# Sheet1.net
KiCad netlist of a schematic drawn in Altium Designer
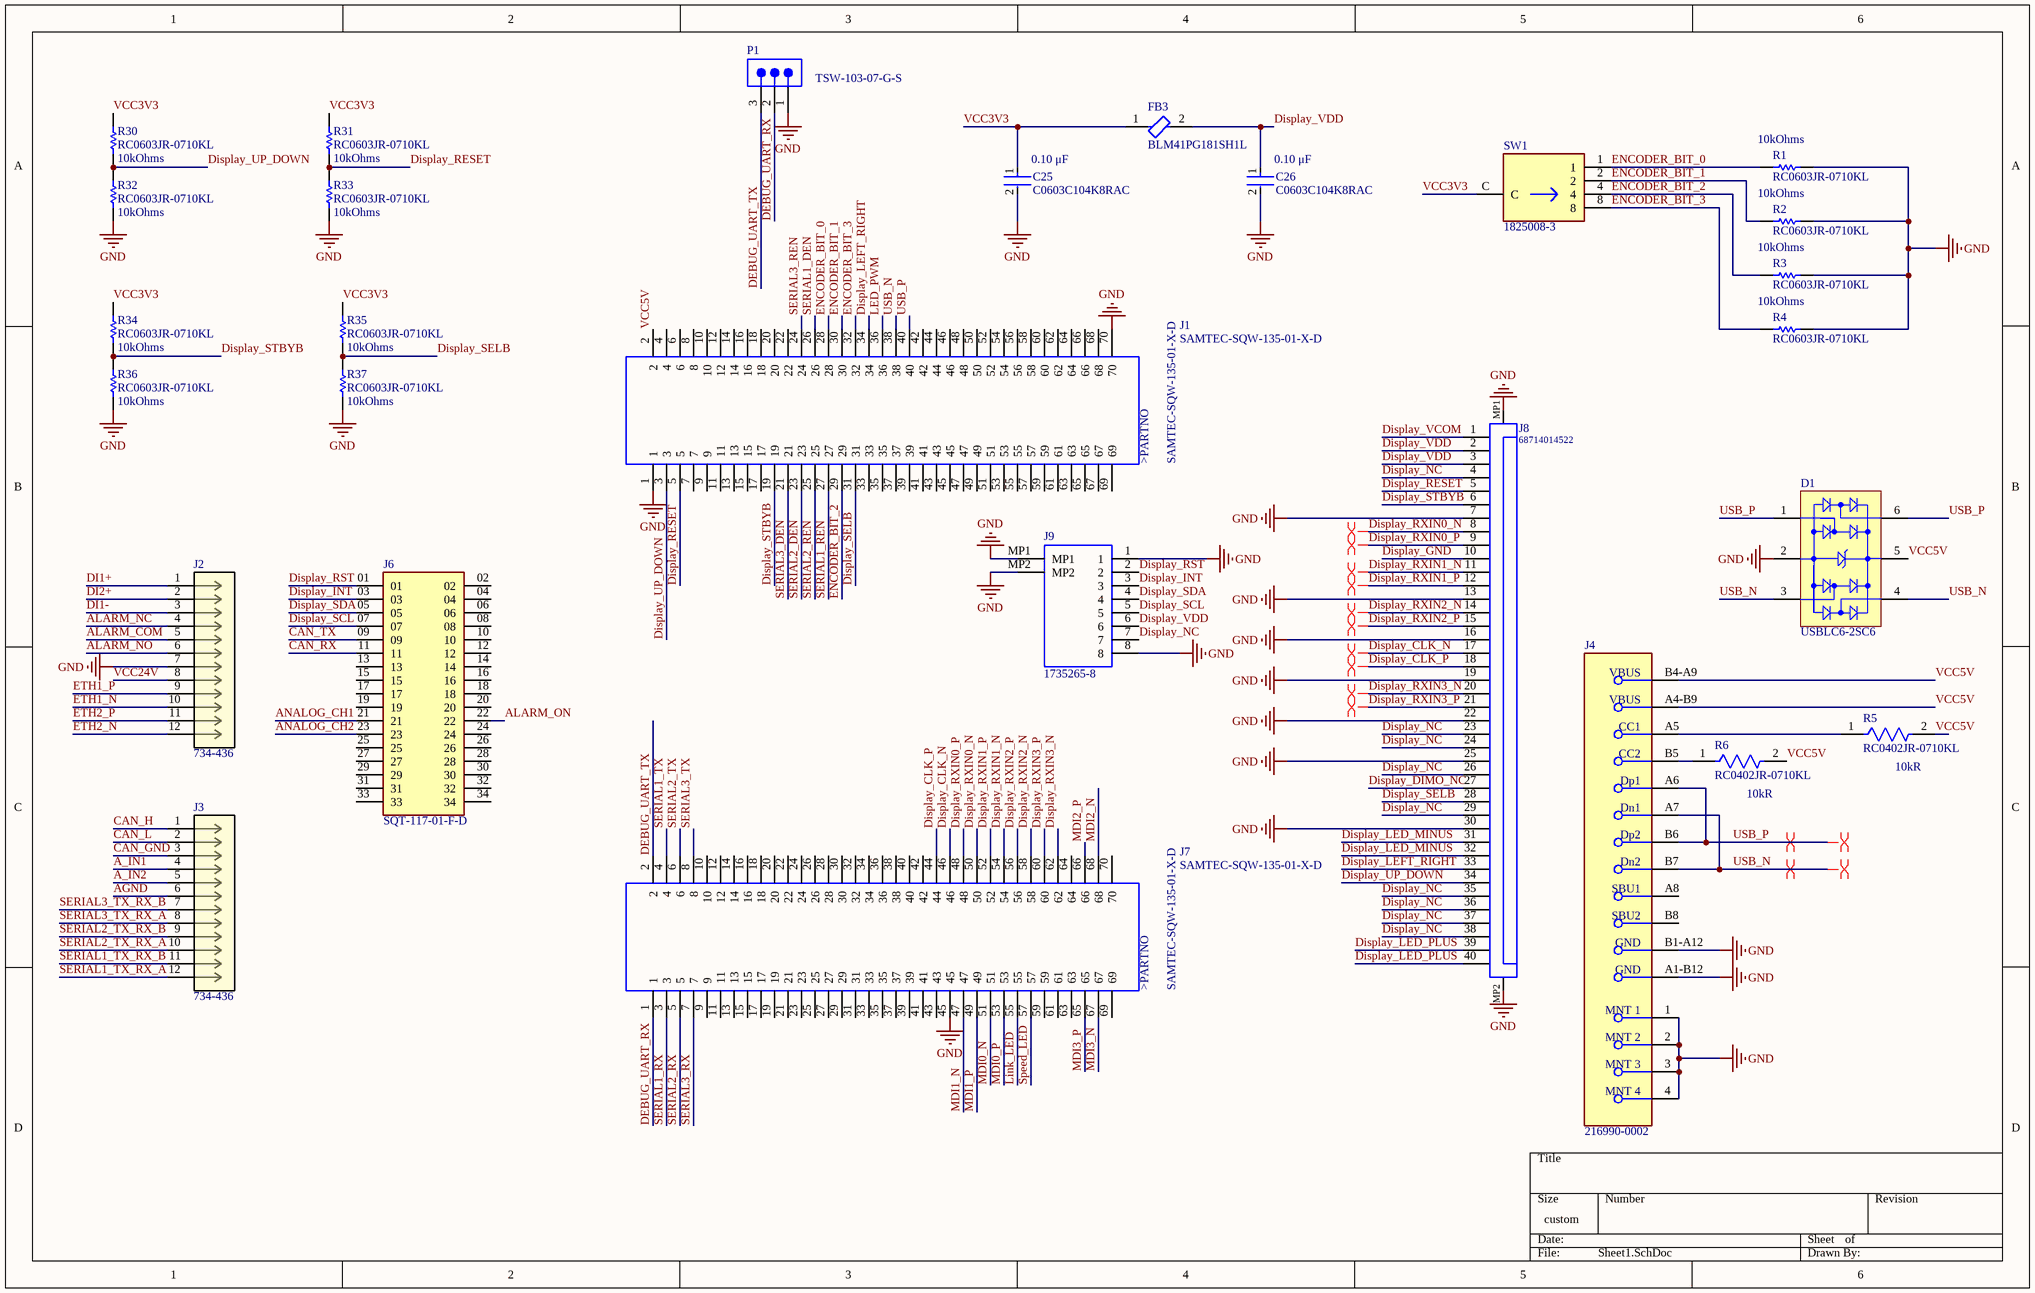
[diagram p0: Sheet1.SchDoc]

(export (version "E")
  (design (tool "Eeschema 10.0.6"))
  (components
    (comp (ref "C25")
      (value "C0603C104K8RAC")
      (footprint "FP-C0603C-CF-MFG")
      (description "C0603 0.10 μF X7R 30ppm/°C 10.00% 10 V")
      (fields
        (field (name "MANUFACTURER") "KEMET")
        (field (name "CAPACITANCE") "0.10 μF")
        (field (name "OCTOPART") "https://octopart.com/c0603c104k8rac-kemet-1325403")
      )
      (libsource (lib "Altium Content Vault") (part "b4654b650e69147ec39a6b967a45e02"))
    )
    (comp (ref "C26")
      (value "C0603C104K8RAC")
      (footprint "FP-C0603C-CF-MFG")
      (description "C0603 0.10 μF X7R 30ppm/°C 10.00% 10 V")
      (fields
        (field (name "MANUFACTURER") "KEMET")
        (field (name "CAPACITANCE") "0.10 μF")
        (field (name "OCTOPART") "https://octopart.com/c0603c104k8rac-kemet-1325403")
      )
      (libsource (lib "Altium Content Vault") (part "b4654b650e69147ec39a6b967a45e02"))
    )
    (comp (ref "D1")
      (value "USBLC6-2SC6")
      (footprint "STM-SOT23-6L_V")
      (description "Very low capacitance ESD protection, 3.5 pF, -40 to 125 degC, 6-Pin SOT23, RoHS, Tape and Reel")
      (fields (field (name "MANUFACTURER") "STMicroelectronics"))
      (libsource (lib "Altium Content Vault") (part "STM-USB_DVI_HDMIULC6-4SC6X-SOT23-6L"))
    )
    (comp (ref "FB3")
      (value "BLM41PG181SH1L")
      (footprint "FP-BLM41-0_2-a1_2-MFG")
      (description "Ferrite Bead, 1806, 180Ω @ 100MHz, 25%, 0.02Ω, 3.5A")
      (fields (field (name "TOLERANCE") "25%"))
      (libsource (lib "Altium Content Vault") (part "5f30dd21d616792df468990f7003faa"))
    )
    (comp (ref "J1")
      (value "SAMTEC-SQW-135-01-X-D")
      (footprint "SAMTEC-SQW-135-01-X-D")
      (libsource (lib "Schlib2") (part "SAMTEC-SQW-135-01-X-D"))
    )
    (comp (ref "J2")
      (value "734-436")
      (footprint "CONN12_734-436_WAG")
      (description "No Description Available")
      (fields (field (name "COPYRIGHT") "Copyright (C) 2022 Ultra Librarian. All rights reserved."))
      (libsource (lib "Schlib2") (part "734-436"))
    )
    (comp (ref "J3")
      (value "734-436")
      (footprint "CONN12_734-436_WAG")
      (description "No Description Available")
      (fields (field (name "COPYRIGHT") "Copyright (C) 2022 Ultra Librarian. All rights reserved."))
      (libsource (lib "Schlib2") (part "734-436"))
    )
    (comp (ref "J4")
      (value "216990-0002")
      (footprint "FP-216990-0002-MFG")
      (description "CONN RCP USB2.0 TYP C 24P SMD RA")
      (libsource (lib "Altium Content Vault") (part "7e081d3bdd84dd7df1daf8a7a06d5b3"))
    )
    (comp (ref "J6")
      (value "SQT-117-01-F-D")
      (footprint "SAMTEC_SQT-117-01-F-D")
      (fields (field (name "MF") "Samtec"))
      (libsource (lib "Schlib2") (part "SQT-117-01-F-D"))
    )
    (comp (ref "J7")
      (value "SAMTEC-SQW-135-01-X-D")
      (footprint "SAMTEC-SQW-135-01-X-D")
      (libsource (lib "Schlib2") (part "SAMTEC-SQW-135-01-X-D"))
    )
    (comp (ref "J8")
      (value "68714014522")
      (footprint "68714014522")
      (description "SMT ZIF Connectors WR-FPC, Horizontal, Bottom Contact, pitch 0.5 mm, 40 pins")
      (fields (field (name "MANUFACTURER") "Wurth Elektronik") (field (name "PUBLISHER") "WurthElektronik"))
      (libsource (lib "Altium Content Vault") (part "WE-6871401XXX22-40"))
    )
    (comp (ref "J9")
      (value "1735265-8")
      (footprint "17352658")
      (description "1MM FPC HORZ.BOTTOM CONT.ASSY 8P (Au)")
      (fields (field (name "MOUSER PART NUMBER") "571-1735265-8"))
      (libsource (lib "Schlib2") (part "1735265-8"))
    )
    (comp (ref "P1")
      (value "TSW-103-07-G-S")
      (footprint "SMTC-TSW-103-07-X-S")
      (description "0.025\" SQ Post Header, Through-hole, Vertical, -55 to 125 degC, 2.54 mm Pitch, 3-Pin, Male, RoHS")
      (fields (field (name "MANUFACTURER") "Samtec"))
      (libsource (lib "Altium Content Vault") (part "SMTC-TSW-103-X-X-S-X"))
    )
    (comp (ref "R1")
      (value "RC0603JR-0710KL")
      (footprint "RESC1608X55X25ML10T15")
      (description "Resistor, 10 KOhm, +/- 5%, 100 mW, -55 to 155 degC, 0603 (1608 Metric), RoHS, Tape and Reel")
      (fields
        (field (name "RESISTANCE") "10kOhms")
        (field (name "MANUFACTURER") "Yageo")
        (field (name "TOLERANCE") "5%")
      )
      (libsource (lib "Altium Content Vault") (part "RES-2"))
    )
    (comp (ref "R2")
      (value "RC0603JR-0710KL")
      (footprint "RESC1608X55X25ML10T15")
      (description "Resistor, 10 KOhm, +/- 5%, 100 mW, -55 to 155 degC, 0603 (1608 Metric), RoHS, Tape and Reel")
      (fields
        (field (name "RESISTANCE") "10kOhms")
        (field (name "MANUFACTURER") "Yageo")
        (field (name "TOLERANCE") "5%")
      )
      (libsource (lib "Altium Content Vault") (part "RES-2"))
    )
    (comp (ref "R3")
      (value "RC0603JR-0710KL")
      (footprint "RESC1608X55X25ML10T15")
      (description "Resistor, 10 KOhm, +/- 5%, 100 mW, -55 to 155 degC, 0603 (1608 Metric), RoHS, Tape and Reel")
      (fields
        (field (name "RESISTANCE") "10kOhms")
        (field (name "MANUFACTURER") "Yageo")
        (field (name "TOLERANCE") "5%")
      )
      (libsource (lib "Altium Content Vault") (part "RES-2"))
    )
    (comp (ref "R4")
      (value "RC0603JR-0710KL")
      (footprint "RESC1608X55X25ML10T15")
      (description "Resistor, 10 KOhm, +/- 5%, 100 mW, -55 to 155 degC, 0603 (1608 Metric), RoHS, Tape and Reel")
      (fields
        (field (name "RESISTANCE") "10kOhms")
        (field (name "MANUFACTURER") "Yageo")
        (field (name "TOLERANCE") "5%")
      )
      (libsource (lib "Altium Content Vault") (part "RES-2"))
    )
    (comp (ref "R5")
      (value "RC0402JR-0710KL")
      (footprint "FP-RC0402-0_4-IPC_C")
      (description "RES 10K OHM 5% 1/16W 0402")
      (fields (field (name "RESISTANCE") "10kR") (field (name "TOLERANCE") "5%"))
      (libsource (lib "Altium Content Vault") (part "1029c3af85768c4190bb7ad29bc67b5"))
    )
    (comp (ref "R6")
      (value "RC0402JR-0710KL")
      (footprint "FP-RC0402-0_4-IPC_C")
      (description "RES 10K OHM 5% 1/16W 0402")
      (fields (field (name "RESISTANCE") "10kR") (field (name "TOLERANCE") "5%"))
      (libsource (lib "Altium Content Vault") (part "1029c3af85768c4190bb7ad29bc67b5"))
    )
    (comp (ref "R30")
      (value "RC0603JR-0710KL")
      (footprint "RESC1608X55X25ML10T15")
      (description "Resistor, 10 KOhm, +/- 5%, 100 mW, -55 to 155 degC, 0603 (1608 Metric), RoHS, Tape and Reel")
      (fields
        (field (name "RESISTANCE") "10kOhms")
        (field (name "MANUFACTURER") "Yageo")
        (field (name "TOLERANCE") "5%")
      )
      (libsource (lib "Altium Content Vault") (part "RES-2"))
    )
    (comp (ref "R31")
      (value "RC0603JR-0710KL")
      (footprint "RESC1608X55X25ML10T15")
      (description "Resistor, 10 KOhm, +/- 5%, 100 mW, -55 to 155 degC, 0603 (1608 Metric), RoHS, Tape and Reel")
      (fields
        (field (name "RESISTANCE") "10kOhms")
        (field (name "MANUFACTURER") "Yageo")
        (field (name "TOLERANCE") "5%")
      )
      (libsource (lib "Altium Content Vault") (part "RES-2"))
    )
    (comp (ref "R32")
      (value "RC0603JR-0710KL")
      (footprint "RESC1608X55X25ML10T15")
      (description "Resistor, 10 KOhm, +/- 5%, 100 mW, -55 to 155 degC, 0603 (1608 Metric), RoHS, Tape and Reel")
      (fields
        (field (name "RESISTANCE") "10kOhms")
        (field (name "MANUFACTURER") "Yageo")
        (field (name "TOLERANCE") "5%")
      )
      (libsource (lib "Altium Content Vault") (part "RES-2"))
    )
    (comp (ref "R33")
      (value "RC0603JR-0710KL")
      (footprint "RESC1608X55X25ML10T15")
      (description "Resistor, 10 KOhm, +/- 5%, 100 mW, -55 to 155 degC, 0603 (1608 Metric), RoHS, Tape and Reel")
      (fields
        (field (name "RESISTANCE") "10kOhms")
        (field (name "MANUFACTURER") "Yageo")
        (field (name "TOLERANCE") "5%")
      )
      (libsource (lib "Altium Content Vault") (part "RES-2"))
    )
    (comp (ref "R34")
      (value "RC0603JR-0710KL")
      (footprint "RESC1608X55X25ML10T15")
      (description "Resistor, 10 KOhm, +/- 5%, 100 mW, -55 to 155 degC, 0603 (1608 Metric), RoHS, Tape and Reel")
      (fields
        (field (name "RESISTANCE") "10kOhms")
        (field (name "MANUFACTURER") "Yageo")
        (field (name "TOLERANCE") "5%")
      )
      (libsource (lib "Altium Content Vault") (part "RES-2"))
    )
    (comp (ref "R35")
      (value "RC0603JR-0710KL")
      (footprint "RESC1608X55X25ML10T15")
      (description "Resistor, 10 KOhm, +/- 5%, 100 mW, -55 to 155 degC, 0603 (1608 Metric), RoHS, Tape and Reel")
      (fields
        (field (name "RESISTANCE") "10kOhms")
        (field (name "MANUFACTURER") "Yageo")
        (field (name "TOLERANCE") "5%")
      )
      (libsource (lib "Altium Content Vault") (part "RES-2"))
    )
    (comp (ref "R36")
      (value "RC0603JR-0710KL")
      (footprint "RESC1608X55X25ML10T15")
      (description "Resistor, 10 KOhm, +/- 5%, 100 mW, -55 to 155 degC, 0603 (1608 Metric), RoHS, Tape and Reel")
      (fields
        (field (name "RESISTANCE") "10kOhms")
        (field (name "MANUFACTURER") "Yageo")
        (field (name "TOLERANCE") "5%")
      )
      (libsource (lib "Altium Content Vault") (part "RES-2"))
    )
    (comp (ref "R37")
      (value "RC0603JR-0710KL")
      (footprint "RESC1608X55X25ML10T15")
      (description "Resistor, 10 KOhm, +/- 5%, 100 mW, -55 to 155 degC, 0603 (1608 Metric), RoHS, Tape and Reel")
      (fields
        (field (name "RESISTANCE") "10kOhms")
        (field (name "MANUFACTURER") "Yageo")
        (field (name "TOLERANCE") "5%")
      )
      (libsource (lib "Altium Content Vault") (part "RES-2"))
    )
    (comp (ref "SW1")
      (value "1825008-3")
      (footprint "FP-1825008-3-MFG")
      (description "SW ROTARY DIP HEX COMP 0.4VA 20V")
      (libsource (lib "Altium Content Vault") (part "f1b16a2328e8568533cbbc73886a3cd"))
    )
  )
  (nets
    (net (code "1") (name "/AGND") (class "Default")
      (node (ref "J3") (pin "6") (pinfunction "6_6") (pintype "passive"))
    )
    (net (code "2") (name "/ALARM_COM") (class "Default")
      (node (ref "J2") (pin "5") (pinfunction "5_5") (pintype "passive"))
    )
    (net (code "3") (name "/ALARM_NC") (class "Default")
      (node (ref "J2") (pin "4") (pinfunction "4_4") (pintype "passive"))
    )
    (net (code "4") (name "/ALARM_NO") (class "Default")
      (node (ref "J2") (pin "6") (pinfunction "6_6") (pintype "passive"))
    )
    (net (code "5") (name "/ALARM_ON") (class "Default")
      (node (ref "J6") (pin "22") (pinfunction "22_22") (pintype "passive"))
    )
    (net (code "6") (name "/ANALOG_CH1") (class "Default")
      (node (ref "J6") (pin "21") (pinfunction "21_21") (pintype "passive"))
    )
    (net (code "7") (name "/ANALOG_CH2") (class "Default")
      (node (ref "J6") (pin "23") (pinfunction "23_23") (pintype "passive"))
    )
    (net (code "8") (name "/A_IN1") (class "Default")
      (node (ref "J3") (pin "4") (pinfunction "4_4") (pintype "passive"))
    )
    (net (code "9") (name "/A_IN2") (class "Default")
      (node (ref "J3") (pin "5") (pinfunction "5_5") (pintype "passive"))
    )
    (net (code "10") (name "/CAN_GND") (class "Default")
      (node (ref "J3") (pin "3") (pinfunction "3_3") (pintype "passive"))
    )
    (net (code "11") (name "/CAN_H") (class "Default")
      (node (ref "J3") (pin "1") (pinfunction "1_1") (pintype "passive"))
    )
    (net (code "12") (name "/CAN_L") (class "Default")
      (node (ref "J3") (pin "2") (pinfunction "2_2") (pintype "passive"))
    )
    (net (code "13") (name "/CAN_RX") (class "Default")
      (node (ref "J6") (pin "11") (pinfunction "11_11") (pintype "passive"))
    )
    (net (code "14") (name "/CAN_TX") (class "Default")
      (node (ref "J6") (pin "09") (pinfunction "09_09") (pintype "passive"))
    )
    (net (code "15") (name "/DEBUG_UART_RX") (class "Default")
      (node (ref "J7") (pin "1") (pinfunction "1_1") (pintype "passive"))
      (node (ref "P1") (pin "2") (pinfunction "2_2") (pintype "passive"))
    )
    (net (code "16") (name "/DEBUG_UART_TX") (class "Default")
      (node (ref "J7") (pin "2") (pinfunction "2_2") (pintype "passive"))
      (node (ref "P1") (pin "3") (pinfunction "3_3") (pintype "passive"))
    )
    (net (code "17") (name "/DI1+") (class "Default")
      (node (ref "J2") (pin "1") (pinfunction "1_1") (pintype "passive"))
    )
    (net (code "18") (name "/DI1-") (class "Default")
      (node (ref "J2") (pin "3") (pinfunction "3_3") (pintype "passive"))
    )
    (net (code "19") (name "/DI2+") (class "Default")
      (node (ref "J2") (pin "2") (pinfunction "2_2") (pintype "passive"))
    )
    (net (code "20") (name "/Display_CLK_N") (class "Default")
      (node (ref "J7") (pin "46") (pinfunction "46_46") (pintype "passive"))
      (node (ref "J8") (pin "17") (pinfunction "17_17") (pintype "passive"))
    )
    (net (code "21") (name "/Display_CLK_P") (class "Default")
      (node (ref "J7") (pin "44") (pinfunction "44_44") (pintype "passive"))
      (node (ref "J8") (pin "18") (pinfunction "18_18") (pintype "passive"))
    )
    (net (code "22") (name "/Display_DIMO_NC") (class "Default")
      (node (ref "J8") (pin "27") (pinfunction "27_27") (pintype "passive"))
    )
    (net (code "23") (name "/Display_GND") (class "Default")
      (node (ref "J8") (pin "10") (pinfunction "10_10") (pintype "passive"))
    )
    (net (code "24") (name "/Display_INT") (class "Default")
      (node (ref "J6") (pin "03") (pinfunction "03_03") (pintype "passive"))
      (node (ref "J9") (pin "3") (pinfunction "3_3") (pintype "passive"))
    )
    (net (code "25") (name "/Display_LED_MINUS") (class "Default")
      (node (ref "J8") (pin "31") (pinfunction "31_31") (pintype "passive"))
      (node (ref "J8") (pin "32") (pinfunction "32_32") (pintype "passive"))
    )
    (net (code "26") (name "/Display_LED_PLUS") (class "Default")
      (node (ref "J8") (pin "39") (pinfunction "39_39") (pintype "passive"))
      (node (ref "J8") (pin "40") (pinfunction "40_40") (pintype "passive"))
    )
    (net (code "27") (name "/Display_LEFT_RIGHT") (class "Default")
      (node (ref "J1") (pin "34") (pinfunction "34_34") (pintype "passive"))
      (node (ref "J8") (pin "33") (pinfunction "33_33") (pintype "passive"))
    )
    (net (code "28") (name "/Display_NC") (class "Default")
      (node (ref "J8") (pin "23") (pinfunction "23_23") (pintype "passive"))
      (node (ref "J8") (pin "24") (pinfunction "24_24") (pintype "passive"))
      (node (ref "J8") (pin "26") (pinfunction "26_26") (pintype "passive"))
      (node (ref "J8") (pin "29") (pinfunction "29_29") (pintype "passive"))
      (node (ref "J8") (pin "35") (pinfunction "35_35") (pintype "passive"))
      (node (ref "J8") (pin "36") (pinfunction "36_36") (pintype "passive"))
      (node (ref "J8") (pin "37") (pinfunction "37_37") (pintype "passive"))
      (node (ref "J8") (pin "38") (pinfunction "38_38") (pintype "passive"))
      (node (ref "J8") (pin "4") (pinfunction "4_4") (pintype "passive"))
      (node (ref "J9") (pin "7") (pinfunction "7_7") (pintype "passive"))
    )
    (net (code "29") (name "/Display_RESET") (class "Default")
      (node (ref "J1") (pin "5") (pinfunction "5_5") (pintype "passive"))
      (node (ref "J8") (pin "5") (pinfunction "5_5") (pintype "passive"))
      (node (ref "R31") (pin "1") (pinfunction "1_1") (pintype "passive"))
      (node (ref "R33") (pin "2") (pinfunction "2_2") (pintype "passive"))
    )
    (net (code "30") (name "/Display_RST") (class "Default")
      (node (ref "J6") (pin "01") (pinfunction "01_01") (pintype "passive"))
      (node (ref "J9") (pin "2") (pinfunction "2_2") (pintype "passive"))
    )
    (net (code "31") (name "/Display_RXIN0_N") (class "Default")
      (node (ref "J7") (pin "50") (pinfunction "50_50") (pintype "passive"))
      (node (ref "J8") (pin "8") (pinfunction "8_8") (pintype "passive"))
    )
    (net (code "32") (name "/Display_RXIN0_P") (class "Default")
      (node (ref "J7") (pin "48") (pinfunction "48_48") (pintype "passive"))
      (node (ref "J8") (pin "9") (pinfunction "9_9") (pintype "passive"))
    )
    (net (code "33") (name "/Display_RXIN1_N") (class "Default")
      (node (ref "J7") (pin "54") (pinfunction "54_54") (pintype "passive"))
      (node (ref "J8") (pin "11") (pinfunction "11_11") (pintype "passive"))
    )
    (net (code "34") (name "/Display_RXIN1_P") (class "Default")
      (node (ref "J7") (pin "52") (pinfunction "52_52") (pintype "passive"))
      (node (ref "J8") (pin "12") (pinfunction "12_12") (pintype "passive"))
    )
    (net (code "35") (name "/Display_RXIN2_N") (class "Default")
      (node (ref "J7") (pin "58") (pinfunction "58_58") (pintype "passive"))
      (node (ref "J8") (pin "14") (pinfunction "14_14") (pintype "passive"))
    )
    (net (code "36") (name "/Display_RXIN2_P") (class "Default")
      (node (ref "J7") (pin "56") (pinfunction "56_56") (pintype "passive"))
      (node (ref "J8") (pin "15") (pinfunction "15_15") (pintype "passive"))
    )
    (net (code "37") (name "/Display_RXIN3_N") (class "Default")
      (node (ref "J7") (pin "62") (pinfunction "62_62") (pintype "passive"))
      (node (ref "J8") (pin "20") (pinfunction "20_20") (pintype "passive"))
    )
    (net (code "38") (name "/Display_RXIN3_P") (class "Default")
      (node (ref "J7") (pin "60") (pinfunction "60_60") (pintype "passive"))
      (node (ref "J8") (pin "21") (pinfunction "21_21") (pintype "passive"))
    )
    (net (code "39") (name "/Display_SCL") (class "Default")
      (node (ref "J6") (pin "07") (pinfunction "07_07") (pintype "passive"))
      (node (ref "J9") (pin "5") (pinfunction "5_5") (pintype "passive"))
    )
    (net (code "40") (name "/Display_SDA") (class "Default")
      (node (ref "J6") (pin "05") (pinfunction "05_05") (pintype "passive"))
      (node (ref "J9") (pin "4") (pinfunction "4_4") (pintype "passive"))
    )
    (net (code "41") (name "/Display_SELB") (class "Default")
      (node (ref "J1") (pin "31") (pinfunction "31_31") (pintype "passive"))
      (node (ref "J8") (pin "28") (pinfunction "28_28") (pintype "passive"))
      (node (ref "R35") (pin "1") (pinfunction "1_1") (pintype "passive"))
      (node (ref "R37") (pin "2") (pinfunction "2_2") (pintype "passive"))
    )
    (net (code "42") (name "/Display_STBYB") (class "Default")
      (node (ref "J1") (pin "19") (pinfunction "19_19") (pintype "passive"))
      (node (ref "J8") (pin "6") (pinfunction "6_6") (pintype "passive"))
      (node (ref "R34") (pin "1") (pinfunction "1_1") (pintype "passive"))
      (node (ref "R36") (pin "2") (pinfunction "2_2") (pintype "passive"))
    )
    (net (code "43") (name "/Display_UP_DOWN") (class "Default")
      (node (ref "J1") (pin "3") (pinfunction "3_3") (pintype "passive"))
      (node (ref "J8") (pin "34") (pinfunction "34_34") (pintype "passive"))
      (node (ref "R30") (pin "1") (pinfunction "1_1") (pintype "passive"))
      (node (ref "R32") (pin "2") (pinfunction "2_2") (pintype "passive"))
    )
    (net (code "44") (name "/Display_VCOM") (class "Default")
      (node (ref "J8") (pin "1") (pinfunction "1_1") (pintype "passive"))
    )
    (net (code "45") (name "/Display_VDD") (class "Default")
      (node (ref "C26") (pin "1") (pinfunction "1_1") (pintype "passive"))
      (node (ref "FB3") (pin "2") (pinfunction "2_2") (pintype "passive"))
      (node (ref "J8") (pin "2") (pinfunction "2_2") (pintype "passive"))
      (node (ref "J8") (pin "3") (pinfunction "3_3") (pintype "passive"))
      (node (ref "J9") (pin "6") (pinfunction "6_6") (pintype "passive"))
    )
    (net (code "46") (name "/ENCODER_BIT_0") (class "Default")
      (node (ref "J1") (pin "28") (pinfunction "28_28") (pintype "passive"))
      (node (ref "R1") (pin "1") (pinfunction "1_1") (pintype "passive"))
      (node (ref "SW1") (pin "1") (pinfunction "1_1") (pintype "passive"))
    )
    (net (code "47") (name "/ENCODER_BIT_1") (class "Default")
      (node (ref "J1") (pin "30") (pinfunction "30_30") (pintype "passive"))
      (node (ref "R2") (pin "1") (pinfunction "1_1") (pintype "passive"))
      (node (ref "SW1") (pin "2") (pinfunction "2_2") (pintype "passive"))
    )
    (net (code "48") (name "/ENCODER_BIT_2") (class "Default")
      (node (ref "J1") (pin "29") (pinfunction "29_29") (pintype "passive"))
      (node (ref "R3") (pin "1") (pinfunction "1_1") (pintype "passive"))
      (node (ref "SW1") (pin "4") (pinfunction "4_4") (pintype "passive"))
    )
    (net (code "49") (name "/ENCODER_BIT_3") (class "Default")
      (node (ref "J1") (pin "32") (pinfunction "32_32") (pintype "passive"))
      (node (ref "R4") (pin "1") (pinfunction "1_1") (pintype "passive"))
      (node (ref "SW1") (pin "8") (pinfunction "8_8") (pintype "passive"))
    )
    (net (code "50") (name "/ETH1_N") (class "Default")
      (node (ref "J2") (pin "10") (pinfunction "10_10") (pintype "passive"))
    )
    (net (code "51") (name "/ETH1_P") (class "Default")
      (node (ref "J2") (pin "9") (pinfunction "9_9") (pintype "passive"))
    )
    (net (code "52") (name "/ETH2_N") (class "Default")
      (node (ref "J2") (pin "12") (pinfunction "12_12") (pintype "passive"))
    )
    (net (code "53") (name "/ETH2_P") (class "Default")
      (node (ref "J2") (pin "11") (pinfunction "11_11") (pintype "passive"))
    )
    (net (code "54") (name "/LED_PWM") (class "Default")
      (node (ref "J1") (pin "36") (pinfunction "36_36") (pintype "passive"))
    )
    (net (code "55") (name "/Link_LED") (class "Default")
      (node (ref "J7") (pin "55") (pinfunction "55_55") (pintype "passive"))
    )
    (net (code "56") (name "/MDI0_N") (class "Default")
      (node (ref "J7") (pin "51") (pinfunction "51_51") (pintype "passive"))
    )
    (net (code "57") (name "/MDI0_P") (class "Default")
      (node (ref "J7") (pin "53") (pinfunction "53_53") (pintype "passive"))
    )
    (net (code "58") (name "/MDI1_N") (class "Default")
      (node (ref "J7") (pin "47") (pinfunction "47_47") (pintype "passive"))
    )
    (net (code "59") (name "/MDI1_P") (class "Default")
      (node (ref "J7") (pin "49") (pinfunction "49_49") (pintype "passive"))
    )
    (net (code "60") (name "/MDI2_N") (class "Default")
      (node (ref "J7") (pin "68") (pinfunction "68_68") (pintype "passive"))
    )
    (net (code "61") (name "/MDI2_P") (class "Default")
      (node (ref "J7") (pin "66") (pinfunction "66_66") (pintype "passive"))
    )
    (net (code "62") (name "/MDI3_N") (class "Default")
      (node (ref "J7") (pin "67") (pinfunction "67_67") (pintype "passive"))
    )
    (net (code "63") (name "/MDI3_P") (class "Default")
      (node (ref "J7") (pin "65") (pinfunction "65_65") (pintype "passive"))
    )
    (net (code "64") (name "/SERIAL1_DEN") (class "Default")
      (node (ref "J1") (pin "26") (pinfunction "26_26") (pintype "passive"))
    )
    (net (code "65") (name "/SERIAL1_REN") (class "Default")
      (node (ref "J1") (pin "27") (pinfunction "27_27") (pintype "passive"))
    )
    (net (code "66") (name "/SERIAL1_RX") (class "Default")
      (node (ref "J7") (pin "3") (pinfunction "3_3") (pintype "passive"))
    )
    (net (code "67") (name "/SERIAL1_TX") (class "Default")
      (node (ref "J7") (pin "4") (pinfunction "4_4") (pintype "passive"))
    )
    (net (code "68") (name "/SERIAL1_TX_RX_A") (class "Default")
      (node (ref "J3") (pin "12") (pinfunction "12_12") (pintype "passive"))
    )
    (net (code "69") (name "/SERIAL1_TX_RX_B") (class "Default")
      (node (ref "J3") (pin "11") (pinfunction "11_11") (pintype "passive"))
    )
    (net (code "70") (name "/SERIAL2_DEN") (class "Default")
      (node (ref "J1") (pin "23") (pinfunction "23_23") (pintype "passive"))
    )
    (net (code "71") (name "/SERIAL2_REN") (class "Default")
      (node (ref "J1") (pin "25") (pinfunction "25_25") (pintype "passive"))
    )
    (net (code "72") (name "/SERIAL2_RX") (class "Default")
      (node (ref "J7") (pin "5") (pinfunction "5_5") (pintype "passive"))
    )
    (net (code "73") (name "/SERIAL2_TX") (class "Default")
      (node (ref "J7") (pin "6") (pinfunction "6_6") (pintype "passive"))
    )
    (net (code "74") (name "/SERIAL2_TX_RX_A") (class "Default")
      (node (ref "J3") (pin "10") (pinfunction "10_10") (pintype "passive"))
    )
    (net (code "75") (name "/SERIAL2_TX_RX_B") (class "Default")
      (node (ref "J3") (pin "9") (pinfunction "9_9") (pintype "passive"))
    )
    (net (code "76") (name "/SERIAL3_DEN") (class "Default")
      (node (ref "J1") (pin "21") (pinfunction "21_21") (pintype "passive"))
    )
    (net (code "77") (name "/SERIAL3_REN") (class "Default")
      (node (ref "J1") (pin "24") (pinfunction "24_24") (pintype "passive"))
    )
    (net (code "78") (name "/SERIAL3_RX") (class "Default")
      (node (ref "J7") (pin "7") (pinfunction "7_7") (pintype "passive"))
    )
    (net (code "79") (name "/SERIAL3_TX") (class "Default")
      (node (ref "J7") (pin "8") (pinfunction "8_8") (pintype "passive"))
    )
    (net (code "80") (name "/SERIAL3_TX_RX_A") (class "Default")
      (node (ref "J3") (pin "8") (pinfunction "8_8") (pintype "passive"))
    )
    (net (code "81") (name "/SERIAL3_TX_RX_B") (class "Default")
      (node (ref "J3") (pin "7") (pinfunction "7_7") (pintype "passive"))
    )
    (net (code "82") (name "/Speed_LED") (class "Default")
      (node (ref "J7") (pin "57") (pinfunction "57_57") (pintype "passive"))
    )
    (net (code "83") (name "/USB_N") (class "Default")
      (node (ref "D1") (pin "3") (pinfunction "I/O_2_3") (pintype "passive"))
      (node (ref "D1") (pin "4") (pinfunction "I/O_3_4") (pintype "passive"))
      (node (ref "J1") (pin "38") (pinfunction "38_38") (pintype "passive"))
      (node (ref "J4") (pin "A7") (pinfunction "Dn1_A7") (pintype "passive"))
      (node (ref "J4") (pin "B7") (pinfunction "Dn2_B7") (pintype "passive"))
    )
    (net (code "84") (name "/USB_P") (class "Default")
      (node (ref "D1") (pin "1") (pinfunction "I/O_1_1") (pintype "passive"))
      (node (ref "D1") (pin "6") (pinfunction "I/O_4_6") (pintype "passive"))
      (node (ref "J1") (pin "40") (pinfunction "40_40") (pintype "passive"))
      (node (ref "J4") (pin "A6") (pinfunction "Dp1_A6") (pintype "passive"))
      (node (ref "J4") (pin "B6") (pinfunction "Dp2_B6") (pintype "passive"))
    )
    (net (code "85") (name "/VCC3V3") (class "Default")
      (node (ref "C25") (pin "1") (pinfunction "1_1") (pintype "passive"))
      (node (ref "FB3") (pin "1") (pinfunction "1_1") (pintype "passive"))
      (node (ref "R30") (pin "2") (pinfunction "2_2") (pintype "passive"))
      (node (ref "R31") (pin "2") (pinfunction "2_2") (pintype "passive"))
      (node (ref "R34") (pin "2") (pinfunction "2_2") (pintype "passive"))
      (node (ref "R35") (pin "2") (pinfunction "2_2") (pintype "passive"))
      (node (ref "SW1") (pin "C") (pinfunction "C_C") (pintype "passive"))
    )
    (net (code "86") (name "/VCC5V") (class "Default")
      (node (ref "D1") (pin "5") (pinfunction "VBUS_5") (pintype "passive"))
      (node (ref "J1") (pin "2") (pinfunction "2_2") (pintype "passive"))
      (node (ref "J4") (pin "A4-B9") (pinfunction "VBUS_A4-B9") (pintype "passive"))
      (node (ref "J4") (pin "B4-A9") (pinfunction "VBUS_B4-A9") (pintype "passive"))
      (node (ref "R5") (pin "2") (pinfunction "2_2") (pintype "passive"))
      (node (ref "R6") (pin "2") (pinfunction "2_2") (pintype "passive"))
    )
    (net (code "87") (name "/VCC24V") (class "Default")
      (node (ref "J2") (pin "8") (pinfunction "8_8") (pintype "passive"))
    )
    (net (code "88") (name "GND") (class "Default")
      (node (ref "C25") (pin "2") (pinfunction "2_2") (pintype "passive"))
      (node (ref "C26") (pin "2") (pinfunction "2_2") (pintype "passive"))
      (node (ref "D1") (pin "2") (pinfunction "GND_2") (pintype "passive"))
      (node (ref "J1") (pin "1") (pinfunction "1_1") (pintype "passive"))
      (node (ref "J1") (pin "70") (pinfunction "70_70") (pintype "passive"))
      (node (ref "J2") (pin "7") (pinfunction "7_7") (pintype "passive"))
      (node (ref "J4") (pin "1") (pinfunction "MNT_1_1") (pintype "passive"))
      (node (ref "J4") (pin "2") (pinfunction "MNT_2_2") (pintype "passive"))
      (node (ref "J4") (pin "3") (pinfunction "MNT_3_3") (pintype "passive"))
      (node (ref "J4") (pin "4") (pinfunction "MNT_4_4") (pintype "passive"))
      (node (ref "J4") (pin "A1-B12") (pinfunction "GND_A1-B12") (pintype "passive"))
      (node (ref "J4") (pin "B1-A12") (pinfunction "GND_B1-A12") (pintype "passive"))
      (node (ref "J7") (pin "45") (pinfunction "45_45") (pintype "passive"))
      (node (ref "J8") (pin "13") (pinfunction "13_13") (pintype "passive"))
      (node (ref "J8") (pin "16") (pinfunction "16_16") (pintype "passive"))
      (node (ref "J8") (pin "19") (pinfunction "19_19") (pintype "passive"))
      (node (ref "J8") (pin "22") (pinfunction "22_22") (pintype "passive"))
      (node (ref "J8") (pin "25") (pinfunction "25_25") (pintype "passive"))
      (node (ref "J8") (pin "30") (pinfunction "30_30") (pintype "passive"))
      (node (ref "J8") (pin "7") (pinfunction "7_7") (pintype "passive"))
      (node (ref "J8") (pin "MP1") (pinfunction "MP1_MP1") (pintype "passive"))
      (node (ref "J8") (pin "MP2") (pinfunction "MP2_MP2") (pintype "passive"))
      (node (ref "J9") (pin "1") (pinfunction "1_1") (pintype "passive"))
      (node (ref "J9") (pin "8") (pinfunction "8_8") (pintype "passive"))
      (node (ref "J9") (pin "MP1") (pinfunction "MP1_MP1") (pintype "passive"))
      (node (ref "J9") (pin "MP2") (pinfunction "MP2_MP2") (pintype "passive"))
      (node (ref "P1") (pin "1") (pinfunction "1_1") (pintype "passive"))
      (node (ref "R1") (pin "2") (pinfunction "2_2") (pintype "passive"))
      (node (ref "R2") (pin "2") (pinfunction "2_2") (pintype "passive"))
      (node (ref "R3") (pin "2") (pinfunction "2_2") (pintype "passive"))
      (node (ref "R32") (pin "1") (pinfunction "1_1") (pintype "passive"))
      (node (ref "R33") (pin "1") (pinfunction "1_1") (pintype "passive"))
      (node (ref "R36") (pin "1") (pinfunction "1_1") (pintype "passive"))
      (node (ref "R37") (pin "1") (pinfunction "1_1") (pintype "passive"))
      (node (ref "R4") (pin "2") (pinfunction "2_2") (pintype "passive"))
    )
    (net (code "89") (name "Net-(J4-CC1)") (class "Default")
      (node (ref "J4") (pin "A5") (pinfunction "CC1_A5") (pintype "passive"))
      (node (ref "R5") (pin "1") (pinfunction "1_1") (pintype "passive"))
    )
    (net (code "90") (name "Net-(J4-CC2)") (class "Default")
      (node (ref "J4") (pin "B5") (pinfunction "CC2_B5") (pintype "passive"))
      (node (ref "R6") (pin "1") (pinfunction "1_1") (pintype "passive"))
    )
    (net (code "91") (name "unconnected-(J1-Pad4)") (class "Default")
      (node (ref "J1") (pin "4") (pinfunction "4_4") (pintype "passive"))
    )
    (net (code "92") (name "unconnected-(J1-Pad6)") (class "Default")
      (node (ref "J1") (pin "6") (pinfunction "6_6") (pintype "passive"))
    )
    (net (code "93") (name "unconnected-(J1-Pad7)") (class "Default")
      (node (ref "J1") (pin "7") (pinfunction "7_7") (pintype "passive"))
    )
    (net (code "94") (name "unconnected-(J1-Pad8)") (class "Default")
      (node (ref "J1") (pin "8") (pinfunction "8_8") (pintype "passive"))
    )
    (net (code "95") (name "unconnected-(J1-Pad9)") (class "Default")
      (node (ref "J1") (pin "9") (pinfunction "9_9") (pintype "passive"))
    )
    (net (code "96") (name "unconnected-(J1-Pad10)") (class "Default")
      (node (ref "J1") (pin "10") (pinfunction "10_10") (pintype "passive"))
    )
    (net (code "97") (name "unconnected-(J1-Pad11)") (class "Default")
      (node (ref "J1") (pin "11") (pinfunction "11_11") (pintype "passive"))
    )
    (net (code "98") (name "unconnected-(J1-Pad12)") (class "Default")
      (node (ref "J1") (pin "12") (pinfunction "12_12") (pintype "passive"))
    )
    (net (code "99") (name "unconnected-(J1-Pad13)") (class "Default")
      (node (ref "J1") (pin "13") (pinfunction "13_13") (pintype "passive"))
    )
    (net (code "100") (name "unconnected-(J1-Pad14)") (class "Default")
      (node (ref "J1") (pin "14") (pinfunction "14_14") (pintype "passive"))
    )
    (net (code "101") (name "unconnected-(J1-Pad15)") (class "Default")
      (node (ref "J1") (pin "15") (pinfunction "15_15") (pintype "passive"))
    )
    (net (code "102") (name "unconnected-(J1-Pad16)") (class "Default")
      (node (ref "J1") (pin "16") (pinfunction "16_16") (pintype "passive"))
    )
    (net (code "103") (name "unconnected-(J1-Pad17)") (class "Default")
      (node (ref "J1") (pin "17") (pinfunction "17_17") (pintype "passive"))
    )
    (net (code "104") (name "unconnected-(J1-Pad18)") (class "Default")
      (node (ref "J1") (pin "18") (pinfunction "18_18") (pintype "passive"))
    )
    (net (code "105") (name "unconnected-(J1-Pad20)") (class "Default")
      (node (ref "J1") (pin "20") (pinfunction "20_20") (pintype "passive"))
    )
    (net (code "106") (name "unconnected-(J1-Pad22)") (class "Default")
      (node (ref "J1") (pin "22") (pinfunction "22_22") (pintype "passive"))
    )
    (net (code "107") (name "unconnected-(J1-Pad33)") (class "Default")
      (node (ref "J1") (pin "33") (pinfunction "33_33") (pintype "passive"))
    )
    (net (code "108") (name "unconnected-(J1-Pad35)") (class "Default")
      (node (ref "J1") (pin "35") (pinfunction "35_35") (pintype "passive"))
    )
    (net (code "109") (name "unconnected-(J1-Pad37)") (class "Default")
      (node (ref "J1") (pin "37") (pinfunction "37_37") (pintype "passive"))
    )
    (net (code "110") (name "unconnected-(J1-Pad39)") (class "Default")
      (node (ref "J1") (pin "39") (pinfunction "39_39") (pintype "passive"))
    )
    (net (code "111") (name "unconnected-(J1-Pad41)") (class "Default")
      (node (ref "J1") (pin "41") (pinfunction "41_41") (pintype "passive"))
    )
    (net (code "112") (name "unconnected-(J1-Pad42)") (class "Default")
      (node (ref "J1") (pin "42") (pinfunction "42_42") (pintype "passive"))
    )
    (net (code "113") (name "unconnected-(J1-Pad43)") (class "Default")
      (node (ref "J1") (pin "43") (pinfunction "43_43") (pintype "passive"))
    )
    (net (code "114") (name "unconnected-(J1-Pad44)") (class "Default")
      (node (ref "J1") (pin "44") (pinfunction "44_44") (pintype "passive"))
    )
    (net (code "115") (name "unconnected-(J1-Pad45)") (class "Default")
      (node (ref "J1") (pin "45") (pinfunction "45_45") (pintype "passive"))
    )
    (net (code "116") (name "unconnected-(J1-Pad46)") (class "Default")
      (node (ref "J1") (pin "46") (pinfunction "46_46") (pintype "passive"))
    )
    (net (code "117") (name "unconnected-(J1-Pad47)") (class "Default")
      (node (ref "J1") (pin "47") (pinfunction "47_47") (pintype "passive"))
    )
    (net (code "118") (name "unconnected-(J1-Pad48)") (class "Default")
      (node (ref "J1") (pin "48") (pinfunction "48_48") (pintype "passive"))
    )
    (net (code "119") (name "unconnected-(J1-Pad49)") (class "Default")
      (node (ref "J1") (pin "49") (pinfunction "49_49") (pintype "passive"))
    )
    (net (code "120") (name "unconnected-(J1-Pad50)") (class "Default")
      (node (ref "J1") (pin "50") (pinfunction "50_50") (pintype "passive"))
    )
    (net (code "121") (name "unconnected-(J1-Pad51)") (class "Default")
      (node (ref "J1") (pin "51") (pinfunction "51_51") (pintype "passive"))
    )
    (net (code "122") (name "unconnected-(J1-Pad52)") (class "Default")
      (node (ref "J1") (pin "52") (pinfunction "52_52") (pintype "passive"))
    )
    (net (code "123") (name "unconnected-(J1-Pad53)") (class "Default")
      (node (ref "J1") (pin "53") (pinfunction "53_53") (pintype "passive"))
    )
    (net (code "124") (name "unconnected-(J1-Pad54)") (class "Default")
      (node (ref "J1") (pin "54") (pinfunction "54_54") (pintype "passive"))
    )
    (net (code "125") (name "unconnected-(J1-Pad55)") (class "Default")
      (node (ref "J1") (pin "55") (pinfunction "55_55") (pintype "passive"))
    )
    (net (code "126") (name "unconnected-(J1-Pad56)") (class "Default")
      (node (ref "J1") (pin "56") (pinfunction "56_56") (pintype "passive"))
    )
    (net (code "127") (name "unconnected-(J1-Pad57)") (class "Default")
      (node (ref "J1") (pin "57") (pinfunction "57_57") (pintype "passive"))
    )
    (net (code "128") (name "unconnected-(J1-Pad58)") (class "Default")
      (node (ref "J1") (pin "58") (pinfunction "58_58") (pintype "passive"))
    )
    (net (code "129") (name "unconnected-(J1-Pad59)") (class "Default")
      (node (ref "J1") (pin "59") (pinfunction "59_59") (pintype "passive"))
    )
    (net (code "130") (name "unconnected-(J1-Pad60)") (class "Default")
      (node (ref "J1") (pin "60") (pinfunction "60_60") (pintype "passive"))
    )
    (net (code "131") (name "unconnected-(J1-Pad61)") (class "Default")
      (node (ref "J1") (pin "61") (pinfunction "61_61") (pintype "passive"))
    )
    (net (code "132") (name "unconnected-(J1-Pad62)") (class "Default")
      (node (ref "J1") (pin "62") (pinfunction "62_62") (pintype "passive"))
    )
    (net (code "133") (name "unconnected-(J1-Pad63)") (class "Default")
      (node (ref "J1") (pin "63") (pinfunction "63_63") (pintype "passive"))
    )
    (net (code "134") (name "unconnected-(J1-Pad64)") (class "Default")
      (node (ref "J1") (pin "64") (pinfunction "64_64") (pintype "passive"))
    )
    (net (code "135") (name "unconnected-(J1-Pad65)") (class "Default")
      (node (ref "J1") (pin "65") (pinfunction "65_65") (pintype "passive"))
    )
    (net (code "136") (name "unconnected-(J1-Pad66)") (class "Default")
      (node (ref "J1") (pin "66") (pinfunction "66_66") (pintype "passive"))
    )
    (net (code "137") (name "unconnected-(J1-Pad67)") (class "Default")
      (node (ref "J1") (pin "67") (pinfunction "67_67") (pintype "passive"))
    )
    (net (code "138") (name "unconnected-(J1-Pad68)") (class "Default")
      (node (ref "J1") (pin "68") (pinfunction "68_68") (pintype "passive"))
    )
    (net (code "139") (name "unconnected-(J1-Pad69)") (class "Default")
      (node (ref "J1") (pin "69") (pinfunction "69_69") (pintype "passive"))
    )
    (net (code "140") (name "unconnected-(J4-SBU1-PadA8)") (class "Default")
      (node (ref "J4") (pin "A8") (pinfunction "SBU1_A8") (pintype "passive"))
    )
    (net (code "141") (name "unconnected-(J4-SBU2-PadB8)") (class "Default")
      (node (ref "J4") (pin "B8") (pinfunction "SBU2_B8") (pintype "passive"))
    )
    (net (code "142") (name "unconnected-(J6-Pad02)") (class "Default")
      (node (ref "J6") (pin "02") (pinfunction "02_02") (pintype "passive"))
    )
    (net (code "143") (name "unconnected-(J6-Pad04)") (class "Default")
      (node (ref "J6") (pin "04") (pinfunction "04_04") (pintype "passive"))
    )
    (net (code "144") (name "unconnected-(J6-Pad06)") (class "Default")
      (node (ref "J6") (pin "06") (pinfunction "06_06") (pintype "passive"))
    )
    (net (code "145") (name "unconnected-(J6-Pad08)") (class "Default")
      (node (ref "J6") (pin "08") (pinfunction "08_08") (pintype "passive"))
    )
    (net (code "146") (name "unconnected-(J6-Pad10)") (class "Default")
      (node (ref "J6") (pin "10") (pinfunction "10_10") (pintype "passive"))
    )
    (net (code "147") (name "unconnected-(J6-Pad12)") (class "Default")
      (node (ref "J6") (pin "12") (pinfunction "12_12") (pintype "passive"))
    )
    (net (code "148") (name "unconnected-(J6-Pad13)") (class "Default")
      (node (ref "J6") (pin "13") (pinfunction "13_13") (pintype "passive"))
    )
    (net (code "149") (name "unconnected-(J6-Pad14)") (class "Default")
      (node (ref "J6") (pin "14") (pinfunction "14_14") (pintype "passive"))
    )
    (net (code "150") (name "unconnected-(J6-Pad15)") (class "Default")
      (node (ref "J6") (pin "15") (pinfunction "15_15") (pintype "passive"))
    )
    (net (code "151") (name "unconnected-(J6-Pad16)") (class "Default")
      (node (ref "J6") (pin "16") (pinfunction "16_16") (pintype "passive"))
    )
    (net (code "152") (name "unconnected-(J6-Pad17)") (class "Default")
      (node (ref "J6") (pin "17") (pinfunction "17_17") (pintype "passive"))
    )
    (net (code "153") (name "unconnected-(J6-Pad18)") (class "Default")
      (node (ref "J6") (pin "18") (pinfunction "18_18") (pintype "passive"))
    )
    (net (code "154") (name "unconnected-(J6-Pad19)") (class "Default")
      (node (ref "J6") (pin "19") (pinfunction "19_19") (pintype "passive"))
    )
    (net (code "155") (name "unconnected-(J6-Pad20)") (class "Default")
      (node (ref "J6") (pin "20") (pinfunction "20_20") (pintype "passive"))
    )
    (net (code "156") (name "unconnected-(J6-Pad24)") (class "Default")
      (node (ref "J6") (pin "24") (pinfunction "24_24") (pintype "passive"))
    )
    (net (code "157") (name "unconnected-(J6-Pad25)") (class "Default")
      (node (ref "J6") (pin "25") (pinfunction "25_25") (pintype "passive"))
    )
    (net (code "158") (name "unconnected-(J6-Pad26)") (class "Default")
      (node (ref "J6") (pin "26") (pinfunction "26_26") (pintype "passive"))
    )
    (net (code "159") (name "unconnected-(J6-Pad27)") (class "Default")
      (node (ref "J6") (pin "27") (pinfunction "27_27") (pintype "passive"))
    )
    (net (code "160") (name "unconnected-(J6-Pad28)") (class "Default")
      (node (ref "J6") (pin "28") (pinfunction "28_28") (pintype "passive"))
    )
    (net (code "161") (name "unconnected-(J6-Pad29)") (class "Default")
      (node (ref "J6") (pin "29") (pinfunction "29_29") (pintype "passive"))
    )
    (net (code "162") (name "unconnected-(J6-Pad30)") (class "Default")
      (node (ref "J6") (pin "30") (pinfunction "30_30") (pintype "passive"))
    )
    (net (code "163") (name "unconnected-(J6-Pad31)") (class "Default")
      (node (ref "J6") (pin "31") (pinfunction "31_31") (pintype "passive"))
    )
    (net (code "164") (name "unconnected-(J6-Pad32)") (class "Default")
      (node (ref "J6") (pin "32") (pinfunction "32_32") (pintype "passive"))
    )
    (net (code "165") (name "unconnected-(J6-Pad33)") (class "Default")
      (node (ref "J6") (pin "33") (pinfunction "33_33") (pintype "passive"))
    )
    (net (code "166") (name "unconnected-(J6-Pad34)") (class "Default")
      (node (ref "J6") (pin "34") (pinfunction "34_34") (pintype "passive"))
    )
    (net (code "167") (name "unconnected-(J7-Pad9)") (class "Default")
      (node (ref "J7") (pin "9") (pinfunction "9_9") (pintype "passive"))
    )
    (net (code "168") (name "unconnected-(J7-Pad10)") (class "Default")
      (node (ref "J7") (pin "10") (pinfunction "10_10") (pintype "passive"))
    )
    (net (code "169") (name "unconnected-(J7-Pad11)") (class "Default")
      (node (ref "J7") (pin "11") (pinfunction "11_11") (pintype "passive"))
    )
    (net (code "170") (name "unconnected-(J7-Pad12)") (class "Default")
      (node (ref "J7") (pin "12") (pinfunction "12_12") (pintype "passive"))
    )
    (net (code "171") (name "unconnected-(J7-Pad13)") (class "Default")
      (node (ref "J7") (pin "13") (pinfunction "13_13") (pintype "passive"))
    )
    (net (code "172") (name "unconnected-(J7-Pad14)") (class "Default")
      (node (ref "J7") (pin "14") (pinfunction "14_14") (pintype "passive"))
    )
    (net (code "173") (name "unconnected-(J7-Pad15)") (class "Default")
      (node (ref "J7") (pin "15") (pinfunction "15_15") (pintype "passive"))
    )
    (net (code "174") (name "unconnected-(J7-Pad16)") (class "Default")
      (node (ref "J7") (pin "16") (pinfunction "16_16") (pintype "passive"))
    )
    (net (code "175") (name "unconnected-(J7-Pad17)") (class "Default")
      (node (ref "J7") (pin "17") (pinfunction "17_17") (pintype "passive"))
    )
    (net (code "176") (name "unconnected-(J7-Pad18)") (class "Default")
      (node (ref "J7") (pin "18") (pinfunction "18_18") (pintype "passive"))
    )
    (net (code "177") (name "unconnected-(J7-Pad19)") (class "Default")
      (node (ref "J7") (pin "19") (pinfunction "19_19") (pintype "passive"))
    )
    (net (code "178") (name "unconnected-(J7-Pad20)") (class "Default")
      (node (ref "J7") (pin "20") (pinfunction "20_20") (pintype "passive"))
    )
    (net (code "179") (name "unconnected-(J7-Pad21)") (class "Default")
      (node (ref "J7") (pin "21") (pinfunction "21_21") (pintype "passive"))
    )
    (net (code "180") (name "unconnected-(J7-Pad22)") (class "Default")
      (node (ref "J7") (pin "22") (pinfunction "22_22") (pintype "passive"))
    )
    (net (code "181") (name "unconnected-(J7-Pad23)") (class "Default")
      (node (ref "J7") (pin "23") (pinfunction "23_23") (pintype "passive"))
    )
    (net (code "182") (name "unconnected-(J7-Pad24)") (class "Default")
      (node (ref "J7") (pin "24") (pinfunction "24_24") (pintype "passive"))
    )
    (net (code "183") (name "unconnected-(J7-Pad25)") (class "Default")
      (node (ref "J7") (pin "25") (pinfunction "25_25") (pintype "passive"))
    )
    (net (code "184") (name "unconnected-(J7-Pad26)") (class "Default")
      (node (ref "J7") (pin "26") (pinfunction "26_26") (pintype "passive"))
    )
    (net (code "185") (name "unconnected-(J7-Pad27)") (class "Default")
      (node (ref "J7") (pin "27") (pinfunction "27_27") (pintype "passive"))
    )
    (net (code "186") (name "unconnected-(J7-Pad28)") (class "Default")
      (node (ref "J7") (pin "28") (pinfunction "28_28") (pintype "passive"))
    )
    (net (code "187") (name "unconnected-(J7-Pad29)") (class "Default")
      (node (ref "J7") (pin "29") (pinfunction "29_29") (pintype "passive"))
    )
    (net (code "188") (name "unconnected-(J7-Pad30)") (class "Default")
      (node (ref "J7") (pin "30") (pinfunction "30_30") (pintype "passive"))
    )
    (net (code "189") (name "unconnected-(J7-Pad31)") (class "Default")
      (node (ref "J7") (pin "31") (pinfunction "31_31") (pintype "passive"))
    )
    (net (code "190") (name "unconnected-(J7-Pad32)") (class "Default")
      (node (ref "J7") (pin "32") (pinfunction "32_32") (pintype "passive"))
    )
    (net (code "191") (name "unconnected-(J7-Pad33)") (class "Default")
      (node (ref "J7") (pin "33") (pinfunction "33_33") (pintype "passive"))
    )
    (net (code "192") (name "unconnected-(J7-Pad34)") (class "Default")
      (node (ref "J7") (pin "34") (pinfunction "34_34") (pintype "passive"))
    )
    (net (code "193") (name "unconnected-(J7-Pad35)") (class "Default")
      (node (ref "J7") (pin "35") (pinfunction "35_35") (pintype "passive"))
    )
    (net (code "194") (name "unconnected-(J7-Pad36)") (class "Default")
      (node (ref "J7") (pin "36") (pinfunction "36_36") (pintype "passive"))
    )
    (net (code "195") (name "unconnected-(J7-Pad37)") (class "Default")
      (node (ref "J7") (pin "37") (pinfunction "37_37") (pintype "passive"))
    )
    (net (code "196") (name "unconnected-(J7-Pad38)") (class "Default")
      (node (ref "J7") (pin "38") (pinfunction "38_38") (pintype "passive"))
    )
    (net (code "197") (name "unconnected-(J7-Pad39)") (class "Default")
      (node (ref "J7") (pin "39") (pinfunction "39_39") (pintype "passive"))
    )
    (net (code "198") (name "unconnected-(J7-Pad40)") (class "Default")
      (node (ref "J7") (pin "40") (pinfunction "40_40") (pintype "passive"))
    )
    (net (code "199") (name "unconnected-(J7-Pad41)") (class "Default")
      (node (ref "J7") (pin "41") (pinfunction "41_41") (pintype "passive"))
    )
    (net (code "200") (name "unconnected-(J7-Pad42)") (class "Default")
      (node (ref "J7") (pin "42") (pinfunction "42_42") (pintype "passive"))
    )
    (net (code "201") (name "unconnected-(J7-Pad43)") (class "Default")
      (node (ref "J7") (pin "43") (pinfunction "43_43") (pintype "passive"))
    )
    (net (code "202") (name "unconnected-(J7-Pad59)") (class "Default")
      (node (ref "J7") (pin "59") (pinfunction "59_59") (pintype "passive"))
    )
    (net (code "203") (name "unconnected-(J7-Pad61)") (class "Default")
      (node (ref "J7") (pin "61") (pinfunction "61_61") (pintype "passive"))
    )
    (net (code "204") (name "unconnected-(J7-Pad63)") (class "Default")
      (node (ref "J7") (pin "63") (pinfunction "63_63") (pintype "passive"))
    )
    (net (code "205") (name "unconnected-(J7-Pad64)") (class "Default")
      (node (ref "J7") (pin "64") (pinfunction "64_64") (pintype "passive"))
    )
    (net (code "206") (name "unconnected-(J7-Pad69)") (class "Default")
      (node (ref "J7") (pin "69") (pinfunction "69_69") (pintype "passive"))
    )
    (net (code "207") (name "unconnected-(J7-Pad70)") (class "Default")
      (node (ref "J7") (pin "70") (pinfunction "70_70") (pintype "passive"))
    )
  )
)
